# design.net
KiCad netlist of a schematic drawn in Altium Designer
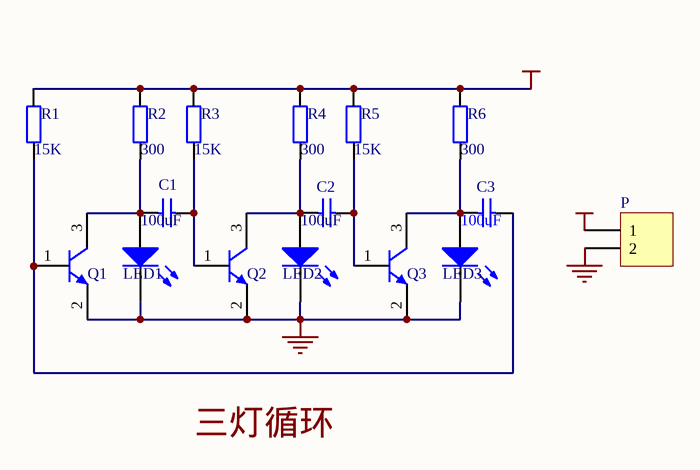
[diagram p0: 三闪灯.SchDoc]

(export (version "E")
  (design (tool "Eeschema 10.0.6"))
  (components
    (comp (ref "C1")
      (value "100uF")
      (footprint "DJDR_5mm")
      (description "Capacitor")
      (fields (field (name "Comment") "Cap") (field (name "PUBLISHER") "Altium Limited"))
      (libsource (lib "Miscellaneous Devices") (part "Cap"))
    )
    (comp (ref "C2")
      (value "100uF")
      (footprint "DJDR_5mm")
      (description "Capacitor")
      (fields (field (name "Comment") "Cap") (field (name "PUBLISHER") "Altium Limited"))
      (libsource (lib "Miscellaneous Devices") (part "Cap"))
    )
    (comp (ref "C3")
      (value "100uF")
      (footprint "DJDR_5mm")
      (description "Capacitor")
      (fields (field (name "Comment") "Cap") (field (name "PUBLISHER") "Altium Limited"))
      (libsource (lib "Miscellaneous Devices") (part "Cap"))
    )
    (comp (ref "LED1")
      (value "LED2")
      (footprint "LED")
      (description "Typical RED, GREEN, YELLOW, AMBER GaAs LED")
      (fields (field (name "PUBLISHER") "Altium Limited"))
      (libsource (lib "Miscellaneous Devices") (part "LED2"))
    )
    (comp (ref "LED2")
      (value "LED2")
      (footprint "LED")
      (description "Typical RED, GREEN, YELLOW, AMBER GaAs LED")
      (fields (field (name "PUBLISHER") "Altium Limited"))
      (libsource (lib "Miscellaneous Devices") (part "LED2"))
    )
    (comp (ref "LED3")
      (value "LED2")
      (footprint "LED")
      (description "Typical RED, GREEN, YELLOW, AMBER GaAs LED")
      (fields (field (name "PUBLISHER") "Altium Limited"))
      (libsource (lib "Miscellaneous Devices") (part "LED2"))
    )
    (comp (ref "P")
      (value "Header 2H")
      (footprint "HDR-2")
      (description "Header, 2-Pin, Right Angle")
      (fields (field (name "PUBLISHER") "Altium Limited"))
      (libsource (lib "Miscellaneous Connectors") (part "Header 2H"))
    )
    (comp (ref "Q1")
      (value "2N3904")
      (footprint "SANJG")
      (description "NPN General Purpose Amplifier")
      (fields (field (name "PUBLISHER") "Altium Limited"))
      (libsource (lib "Miscellaneous Devices") (part "2N3904"))
    )
    (comp (ref "Q2")
      (value "2N3904")
      (footprint "SANJG")
      (description "NPN General Purpose Amplifier")
      (fields (field (name "PUBLISHER") "Altium Limited"))
      (libsource (lib "Miscellaneous Devices") (part "2N3904"))
    )
    (comp (ref "Q3")
      (value "2N3904")
      (footprint "SANJG")
      (description "NPN General Purpose Amplifier")
      (fields (field (name "PUBLISHER") "Altium Limited"))
      (libsource (lib "Miscellaneous Devices") (part "2N3904"))
    )
    (comp (ref "R1")
      (value "15K")
      (footprint "RSE")
      (description "Resistor")
      (fields (field (name "Comment") "Res2") (field (name "PUBLISHER") "Altium Limited"))
      (libsource (lib "Miscellaneous Devices") (part "Res2"))
    )
    (comp (ref "R2")
      (value "300")
      (footprint "RSE")
      (description "Resistor")
      (fields (field (name "Comment") "Res2") (field (name "PUBLISHER") "Altium Limited"))
      (libsource (lib "Miscellaneous Devices") (part "Res2"))
    )
    (comp (ref "R3")
      (value "15K")
      (footprint "RSE")
      (description "Resistor")
      (fields (field (name "Comment") "Res2") (field (name "PUBLISHER") "Altium Limited"))
      (libsource (lib "Miscellaneous Devices") (part "Res2"))
    )
    (comp (ref "R4")
      (value "300")
      (footprint "RSE")
      (description "Resistor")
      (fields (field (name "Comment") "Res2") (field (name "PUBLISHER") "Altium Limited"))
      (libsource (lib "Miscellaneous Devices") (part "Res2"))
    )
    (comp (ref "R5")
      (value "15K")
      (footprint "RSE")
      (description "Resistor")
      (fields (field (name "Comment") "Res2") (field (name "PUBLISHER") "Altium Limited"))
      (libsource (lib "Miscellaneous Devices") (part "Res2"))
    )
    (comp (ref "R6")
      (value "300")
      (footprint "RSE")
      (description "Resistor")
      (fields (field (name "Comment") "Res2") (field (name "PUBLISHER") "Altium Limited"))
      (libsource (lib "Miscellaneous Devices") (part "Res2"))
    )
  )
  (nets
    (net (code "2") (name "GND") (class "Default")
      (node (ref "LED1") (pin "2") (pinfunction "K_2") (pintype "passive"))
      (node (ref "LED2") (pin "2") (pinfunction "K_2") (pintype "passive"))
      (node (ref "LED3") (pin "2") (pinfunction "K_2") (pintype "passive"))
      (node (ref "P") (pin "2") (pinfunction "2_2") (pintype "passive"))
      (node (ref "Q1") (pin "2") (pinfunction "E_2") (pintype "passive"))
      (node (ref "Q2") (pin "2") (pinfunction "E_2") (pintype "passive"))
      (node (ref "Q3") (pin "2") (pinfunction "E_2") (pintype "passive"))
    )
    (net (code "3") (name "Net-(LED1-A)") (class "Default")
      (node (ref "C1") (pin "1") (pinfunction "1_1") (pintype "passive"))
      (node (ref "LED1") (pin "1") (pinfunction "A_1") (pintype "passive"))
      (node (ref "Q1") (pin "3") (pinfunction "C_3") (pintype "passive"))
      (node (ref "R2") (pin "1") (pinfunction "1_1") (pintype "passive"))
    )
    (net (code "4") (name "Net-(LED2-A)") (class "Default")
      (node (ref "C2") (pin "1") (pinfunction "1_1") (pintype "passive"))
      (node (ref "LED2") (pin "1") (pinfunction "A_1") (pintype "passive"))
      (node (ref "Q2") (pin "3") (pinfunction "C_3") (pintype "passive"))
      (node (ref "R4") (pin "1") (pinfunction "1_1") (pintype "passive"))
    )
    (net (code "5") (name "Net-(LED3-A)") (class "Default")
      (node (ref "C3") (pin "1") (pinfunction "1_1") (pintype "passive"))
      (node (ref "LED3") (pin "1") (pinfunction "A_1") (pintype "passive"))
      (node (ref "Q3") (pin "3") (pinfunction "C_3") (pintype "passive"))
      (node (ref "R6") (pin "1") (pinfunction "1_1") (pintype "passive"))
    )
    (net (code "6") (name "Net-(Q1-B)") (class "Default")
      (node (ref "C3") (pin "2") (pinfunction "2_2") (pintype "passive"))
      (node (ref "Q1") (pin "1") (pinfunction "B_1") (pintype "passive"))
      (node (ref "R1") (pin "1") (pinfunction "1_1") (pintype "passive"))
    )
    (net (code "7") (name "Net-(Q2-B)") (class "Default")
      (node (ref "C1") (pin "2") (pinfunction "2_2") (pintype "passive"))
      (node (ref "Q2") (pin "1") (pinfunction "B_1") (pintype "passive"))
      (node (ref "R3") (pin "1") (pinfunction "1_1") (pintype "passive"))
    )
    (net (code "8") (name "Net-(Q3-B)") (class "Default")
      (node (ref "C2") (pin "2") (pinfunction "2_2") (pintype "passive"))
      (node (ref "Q3") (pin "1") (pinfunction "B_1") (pintype "passive"))
      (node (ref "R5") (pin "1") (pinfunction "1_1") (pintype "passive"))
    )
    (net (code "9") (name "VCC") (class "Default")
      (node (ref "P") (pin "1") (pinfunction "1_1") (pintype "passive"))
      (node (ref "R1") (pin "2") (pinfunction "2_2") (pintype "passive"))
      (node (ref "R2") (pin "2") (pinfunction "2_2") (pintype "passive"))
      (node (ref "R3") (pin "2") (pinfunction "2_2") (pintype "passive"))
      (node (ref "R4") (pin "2") (pinfunction "2_2") (pintype "passive"))
      (node (ref "R5") (pin "2") (pinfunction "2_2") (pintype "passive"))
      (node (ref "R6") (pin "2") (pinfunction "2_2") (pintype "passive"))
    )
  )
)
